# nrf51822.net
KiCad netlist of a schematic drawn in EAGLE
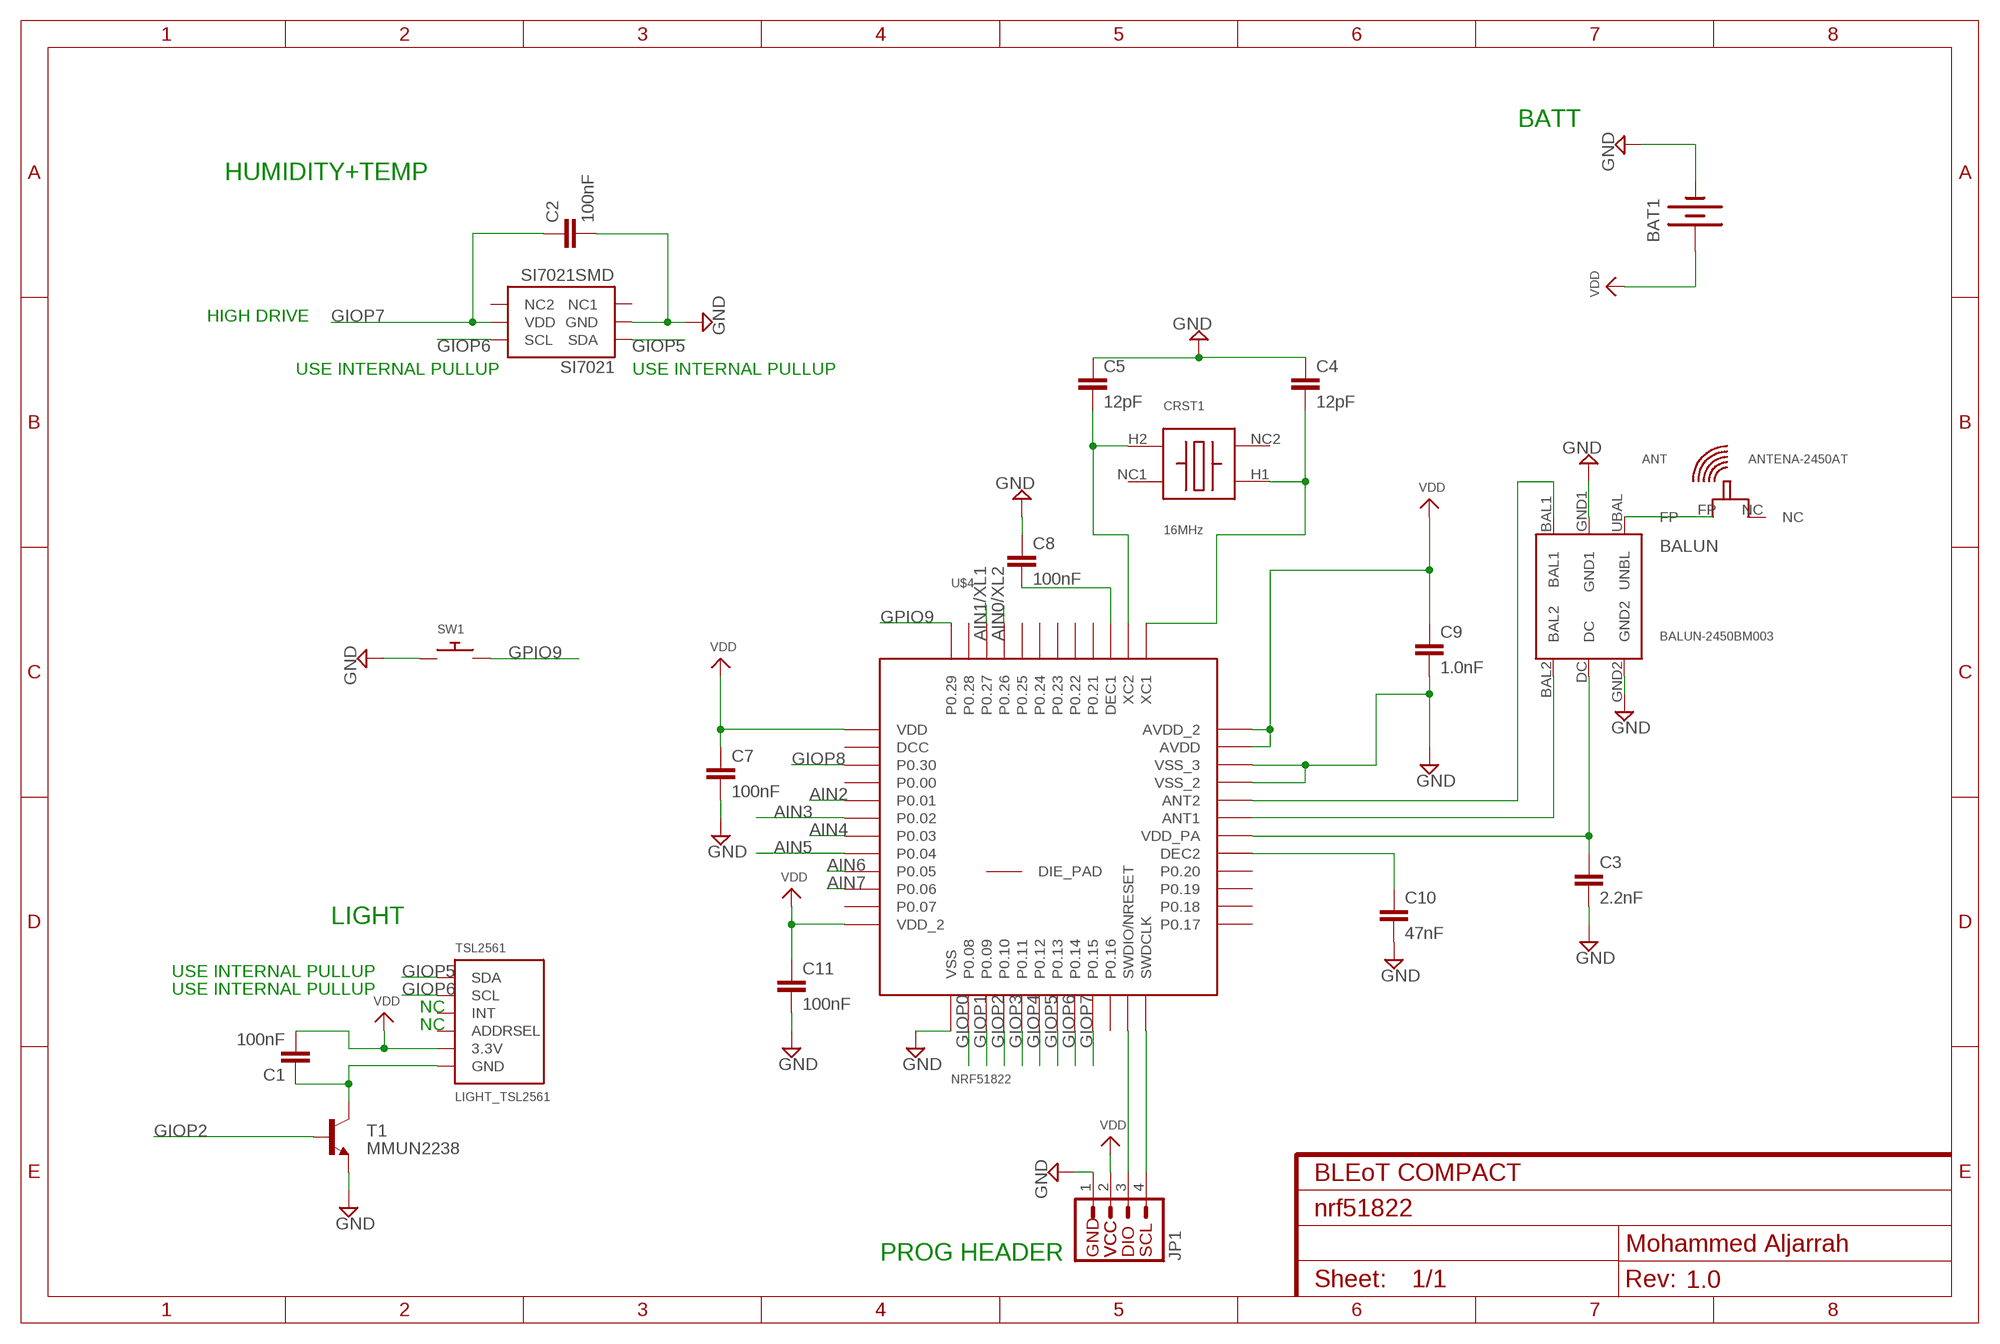
[diagram p0: schematic, sheet 1]

(export (version "E")
  (design (tool "Eeschema 10.0.6"))
  (components
    (comp (ref "ANT")
      (value "ANTENA-2450AT")
      (footprint "eagle-import:2450AT18B100")
      (libsource (lib "eagle-import") (part "ANTENA-2450AT"))
    )
    (comp (ref "BALUN")
      (value "BALUN-2450BM003")
      (footprint "eagle-import:2450BM14E0003")
      (libsource (lib "eagle-import") (part "BALUN-2450BM003"))
    )
    (comp (ref "BAT1")
      (value "BATTERY245PTH")
      (footprint "eagle-import:BATTCON_245MM_PTH")
      (libsource (lib "eagle-import") (part "BATTERY245PTH"))
    )
    (comp (ref "C1")
      (value "100nF")
      (footprint "eagle-import:C0805")
      (libsource (lib "eagle-import") (part "C-EUC0805"))
    )
    (comp (ref "C2")
      (value "100nF")
      (footprint "eagle-import:C0805")
      (libsource (lib "eagle-import") (part "C-EUC0805"))
    )
    (comp (ref "C3")
      (value "2.2nF")
      (footprint "eagle-import:C0805")
      (libsource (lib "eagle-import") (part "C-EUC0805"))
    )
    (comp (ref "C4")
      (value "12pF")
      (footprint "eagle-import:C0805")
      (libsource (lib "eagle-import") (part "C-EUC0805"))
    )
    (comp (ref "C5")
      (value "12pF")
      (footprint "eagle-import:C0805")
      (libsource (lib "eagle-import") (part "C-EUC0805"))
    )
    (comp (ref "C7")
      (value "100nF")
      (footprint "eagle-import:C0805")
      (libsource (lib "eagle-import") (part "C-EUC0805"))
    )
    (comp (ref "C8")
      (value "100nF")
      (footprint "eagle-import:C0805")
      (libsource (lib "eagle-import") (part "C-EUC0805"))
    )
    (comp (ref "C9")
      (value "1.0nF")
      (footprint "eagle-import:C0805")
      (libsource (lib "eagle-import") (part "C-EUC0805"))
    )
    (comp (ref "C10")
      (value "47nF")
      (footprint "eagle-import:C0805")
      (libsource (lib "eagle-import") (part "C-EUC0805"))
    )
    (comp (ref "C11")
      (value "100nF")
      (footprint "eagle-import:C0805")
      (libsource (lib "eagle-import") (part "C-EUC0805"))
    )
    (comp (ref "CRST1")
      (value "16MHz")
      (footprint "eagle-import:CRYSTAL16MHZ")
      (libsource (lib "eagle-import") (part "CX3225GB"))
    )
    (comp (ref "JP1")
      (value "PROG_HEADER")
      (footprint "eagle-import:1X04")
      (libsource (lib "eagle-import") (part "PROG_HEADER"))
    )
    (comp (ref "SI7021")
      (value "SI7021SMD")
      (footprint "eagle-import:SI7021")
      (libsource (lib "eagle-import") (part "SI7021SMD"))
    )
    (comp (ref "SW1")
      (value "SWITCH_PUSHBUTTONSOFTTOUCHSMD_SJ")
      (footprint "eagle-import:PUSHBUTTON_SMD_SJ")
      (libsource (lib "eagle-import") (part "SWITCH_PUSHBUTTONSOFTTOUCHSMD_SJ"))
    )
    (comp (ref "T1")
      (value "MMUN2238")
      (footprint "eagle-import:SOT23-3")
      (libsource (lib "eagle-import") (part "TRANSISTOR_NPNMMBT2222A"))
    )
    (comp (ref "TSL2561")
      (value "LIGHT_TSL2561")
      (footprint "eagle-import:TSL2561_FN")
      (libsource (lib "eagle-import") (part "LIGHT_TSL2561"))
    )
    (comp (ref "U$4")
      (value "NRF51822")
      (footprint "eagle-import:QFN48")
      (libsource (lib "eagle-import") (part "NRF51822"))
    )
  )
  (nets
    (net (code "1") (name "/AIN0{slash}XL2") (class "Default")
      (node (ref "U$4") (pin "45") (pinfunction "P0.26_45") (pintype "bidirectional"))
    )
    (net (code "2") (name "/AIN1{slash}XL1") (class "Default")
      (node (ref "U$4") (pin "46") (pinfunction "P0.27_46") (pintype "bidirectional"))
    )
    (net (code "3") (name "/AIN2") (class "Default")
      (node (ref "U$4") (pin "5") (pinfunction "P0.01_5") (pintype "bidirectional"))
    )
    (net (code "4") (name "/AIN3") (class "Default")
      (node (ref "U$4") (pin "6") (pinfunction "P0.02_6") (pintype "bidirectional"))
    )
    (net (code "5") (name "/AIN4") (class "Default")
      (node (ref "U$4") (pin "7") (pinfunction "P0.03_7") (pintype "bidirectional"))
    )
    (net (code "6") (name "/AIN5") (class "Default")
      (node (ref "U$4") (pin "8") (pinfunction "P0.04_8") (pintype "bidirectional"))
    )
    (net (code "7") (name "/AIN6") (class "Default")
      (node (ref "U$4") (pin "9") (pinfunction "P0.05_9") (pintype "bidirectional"))
    )
    (net (code "8") (name "/AIN7") (class "Default")
      (node (ref "U$4") (pin "10") (pinfunction "P0.06_10") (pintype "bidirectional"))
    )
    (net (code "9") (name "/GIOP0") (class "Default")
      (node (ref "U$4") (pin "14") (pinfunction "P0.08_14") (pintype "bidirectional"))
    )
    (net (code "10") (name "/GIOP1") (class "Default")
      (node (ref "U$4") (pin "15") (pinfunction "P0.09_15") (pintype "bidirectional"))
    )
    (net (code "11") (name "/GIOP2") (class "Default")
      (node (ref "T1") (pin "1") (pinfunction "B_1") (pintype "passive"))
      (node (ref "U$4") (pin "16") (pinfunction "P0.10_16") (pintype "bidirectional"))
    )
    (net (code "12") (name "/GIOP3") (class "Default")
      (node (ref "U$4") (pin "17") (pinfunction "P0.11_17") (pintype "bidirectional"))
    )
    (net (code "13") (name "/GIOP4") (class "Default")
      (node (ref "U$4") (pin "18") (pinfunction "P0.12_18") (pintype "bidirectional"))
    )
    (net (code "14") (name "/GIOP5") (class "Default")
      (node (ref "SI7021") (pin "1") (pinfunction "SDA_1") (pintype "bidirectional"))
      (node (ref "TSL2561") (pin "DATA") (pinfunction "SDA_DATA") (pintype "bidirectional"))
      (node (ref "U$4") (pin "19") (pinfunction "P0.13_19") (pintype "bidirectional"))
    )
    (net (code "15") (name "/GIOP6") (class "Default")
      (node (ref "SI7021") (pin "6") (pinfunction "SCL_6") (pintype "bidirectional"))
      (node (ref "TSL2561") (pin "CLK") (pinfunction "SCL_CLK") (pintype "bidirectional"))
      (node (ref "U$4") (pin "20") (pinfunction "P0.14_20") (pintype "bidirectional"))
    )
    (net (code "16") (name "/GIOP7") (class "Default")
      (node (ref "C2") (pin "1") (pinfunction "1_1") (pintype "passive"))
      (node (ref "SI7021") (pin "5") (pinfunction "VDD_5") (pintype "power_in"))
      (node (ref "U$4") (pin "21") (pinfunction "P0.15_21") (pintype "bidirectional"))
    )
    (net (code "17") (name "/GIOP8") (class "Default")
      (node (ref "U$4") (pin "3") (pinfunction "P0.30_3") (pintype "bidirectional"))
    )
    (net (code "18") (name "/GPIO9") (class "Default")
      (node (ref "SW1") (pin "P$2") (pinfunction "P$2_P$2") (pintype "passive"))
      (node (ref "U$4") (pin "48") (pinfunction "P0.29_48") (pintype "bidirectional"))
    )
    (net (code "19") (name "GND") (class "Default")
      (node (ref "BALUN") (pin "GND1") (pinfunction "GND1_GND1") (pintype "power_in"))
      (node (ref "BALUN") (pin "GND2") (pinfunction "GND2_GND2") (pintype "power_in"))
      (node (ref "BAT1") (pin "2") (pinfunction "-_2") (pintype "power_in"))
      (node (ref "C10") (pin "2") (pinfunction "2_2") (pintype "passive"))
      (node (ref "C11") (pin "2") (pinfunction "2_2") (pintype "passive"))
      (node (ref "C2") (pin "2") (pinfunction "2_2") (pintype "passive"))
      (node (ref "C3") (pin "2") (pinfunction "2_2") (pintype "passive"))
      (node (ref "C4") (pin "1") (pinfunction "1_1") (pintype "passive"))
      (node (ref "C5") (pin "1") (pinfunction "1_1") (pintype "passive"))
      (node (ref "C7") (pin "2") (pinfunction "2_2") (pintype "passive"))
      (node (ref "C8") (pin "1") (pinfunction "1_1") (pintype "passive"))
      (node (ref "C9") (pin "2") (pinfunction "2_2") (pintype "passive"))
      (node (ref "JP1") (pin "1") (pinfunction "1_1") (pintype "passive"))
      (node (ref "SI7021") (pin "2") (pinfunction "GND_2") (pintype "power_in"))
      (node (ref "SW1") (pin "P$1") (pinfunction "P$1_P$1") (pintype "passive"))
      (node (ref "T1") (pin "2") (pinfunction "E_2") (pintype "passive"))
      (node (ref "U$4") (pin "13") (pinfunction "VSS_13") (pintype "power_in"))
      (node (ref "U$4") (pin "33") (pinfunction "VSS_2_33") (pintype "power_in"))
      (node (ref "U$4") (pin "34") (pinfunction "VSS_3_34") (pintype "power_in"))
    )
    (net (code "20") (name "Net-(BALUN-UNBL)") (class "Default")
      (node (ref "ANT") (pin "FP") (pinfunction "FP_FP") (pintype "input"))
      (node (ref "BALUN") (pin "UBAL") (pinfunction "UNBL_UBAL") (pintype "output"))
    )
    (net (code "21") (name "Net-(T1-C)") (class "Default")
      (node (ref "C1") (pin "1") (pinfunction "1_1") (pintype "passive"))
      (node (ref "T1") (pin "3") (pinfunction "C_3") (pintype "passive"))
      (node (ref "TSL2561") (pin "VSS") (pinfunction "GND_VSS") (pintype "bidirectional"))
    )
    (net (code "22") (name "Net-(U$4-ANT1)") (class "Default")
      (node (ref "BALUN") (pin "BAL2") (pinfunction "BAL2_BAL2") (pintype "input"))
      (node (ref "U$4") (pin "31") (pinfunction "ANT1_31") (pintype "bidirectional"))
    )
    (net (code "23") (name "Net-(U$4-ANT2)") (class "Default")
      (node (ref "BALUN") (pin "BAL1") (pinfunction "BAL1_BAL1") (pintype "input"))
      (node (ref "U$4") (pin "32") (pinfunction "ANT2_32") (pintype "bidirectional"))
    )
    (net (code "24") (name "Net-(U$4-DEC1)") (class "Default")
      (node (ref "C8") (pin "2") (pinfunction "2_2") (pintype "passive"))
      (node (ref "U$4") (pin "39") (pinfunction "DEC1_39") (pintype "bidirectional"))
    )
    (net (code "25") (name "Net-(U$4-DEC2)") (class "Default")
      (node (ref "C10") (pin "1") (pinfunction "1_1") (pintype "passive"))
      (node (ref "U$4") (pin "29") (pinfunction "DEC2_29") (pintype "bidirectional"))
    )
    (net (code "26") (name "Net-(U$4-SWDCLK)") (class "Default")
      (node (ref "JP1") (pin "4") (pinfunction "4_4") (pintype "passive"))
      (node (ref "U$4") (pin "24") (pinfunction "SWDCLK_24") (pintype "bidirectional"))
    )
    (net (code "27") (name "Net-(U$4-SWDIO{slash}NRESET)") (class "Default")
      (node (ref "JP1") (pin "3") (pinfunction "3_3") (pintype "passive"))
      (node (ref "U$4") (pin "23") (pinfunction "SWDIO/NRESET_23") (pintype "bidirectional"))
    )
    (net (code "28") (name "Net-(U$4-VDD_PA)") (class "Default")
      (node (ref "BALUN") (pin "DC") (pinfunction "DC_DC") (pintype "power_in"))
      (node (ref "C3") (pin "1") (pinfunction "1_1") (pintype "passive"))
      (node (ref "U$4") (pin "30") (pinfunction "VDD_PA_30") (pintype "bidirectional"))
    )
    (net (code "29") (name "Net-(U$4-XC1)") (class "Default")
      (node (ref "C4") (pin "2") (pinfunction "2_2") (pintype "passive"))
      (node (ref "CRST1") (pin "H1") (pinfunction "H1_H1") (pintype "input"))
      (node (ref "U$4") (pin "37") (pinfunction "XC1_37") (pintype "bidirectional"))
    )
    (net (code "30") (name "Net-(U$4-XC2)") (class "Default")
      (node (ref "C5") (pin "2") (pinfunction "2_2") (pintype "passive"))
      (node (ref "CRST1") (pin "H2") (pinfunction "H2_H2") (pintype "input"))
      (node (ref "U$4") (pin "38") (pinfunction "XC2_38") (pintype "bidirectional"))
    )
    (net (code "31") (name "VDD") (class "Default")
      (node (ref "BAT1") (pin "1") (pinfunction "+_1") (pintype "power_in"))
      (node (ref "BAT1") (pin "3") (pinfunction "+_3") (pintype "power_in"))
      (node (ref "C1") (pin "2") (pinfunction "2_2") (pintype "passive"))
      (node (ref "C11") (pin "1") (pinfunction "1_1") (pintype "passive"))
      (node (ref "C7") (pin "1") (pinfunction "1_1") (pintype "passive"))
      (node (ref "C9") (pin "1") (pinfunction "1_1") (pintype "passive"))
      (node (ref "JP1") (pin "2") (pinfunction "2_2") (pintype "passive"))
      (node (ref "TSL2561") (pin "VDD") (pinfunction "3.3V_VDD") (pintype "bidirectional"))
      (node (ref "U$4") (pin "1") (pinfunction "VDD_1") (pintype "power_in"))
      (node (ref "U$4") (pin "12") (pinfunction "VDD_2_12") (pintype "power_in"))
      (node (ref "U$4") (pin "35") (pinfunction "AVDD_35") (pintype "power_in"))
      (node (ref "U$4") (pin "36") (pinfunction "AVDD_2_36") (pintype "power_in"))
    )
    (net (code "32") (name "unconnected-(ANT-PadNC)") (class "Default")
      (node (ref "ANT") (pin "NC") (pinfunction "NC_NC") (pintype "no_connect"))
    )
    (net (code "33") (name "unconnected-(CRST1-PadNC1)") (class "Default")
      (node (ref "CRST1") (pin "NC1") (pinfunction "NC1_NC1") (pintype "no_connect"))
    )
    (net (code "34") (name "unconnected-(CRST1-PadNC2)") (class "Default")
      (node (ref "CRST1") (pin "NC2") (pinfunction "NC2_NC2") (pintype "no_connect"))
    )
    (net (code "35") (name "unconnected-(SI7021-NC1-Pad3)") (class "Default")
      (node (ref "SI7021") (pin "3") (pinfunction "NC1_3") (pintype "no_connect"))
    )
    (net (code "36") (name "unconnected-(SI7021-NC2-Pad4)") (class "Default")
      (node (ref "SI7021") (pin "4") (pinfunction "NC2_4") (pintype "no_connect"))
    )
    (net (code "37") (name "unconnected-(TSL2561-ADDRSEL-PadADR)") (class "Default")
      (node (ref "TSL2561") (pin "ADR") (pinfunction "ADDRSEL_ADR") (pintype "bidirectional"))
    )
    (net (code "38") (name "unconnected-(TSL2561-PadINT)") (class "Default")
      (node (ref "TSL2561") (pin "INT") (pinfunction "INT_INT") (pintype "bidirectional"))
    )
    (net (code "39") (name "unconnected-(U$4-DCC-Pad2)") (class "Default")
      (node (ref "U$4") (pin "2") (pinfunction "DCC_2") (pintype "no_connect"))
    )
    (net (code "40") (name "unconnected-(U$4-DIE_PAD-PadGND)") (class "Default")
      (node (ref "U$4") (pin "GND") (pinfunction "DIE_PAD_GND") (pintype "bidirectional"))
    )
    (net (code "41") (name "unconnected-(U$4-P0.00-Pad4)") (class "Default")
      (node (ref "U$4") (pin "4") (pinfunction "P0.00_4") (pintype "bidirectional"))
    )
    (net (code "42") (name "unconnected-(U$4-P0.07-Pad11)") (class "Default")
      (node (ref "U$4") (pin "11") (pinfunction "P0.07_11") (pintype "bidirectional"))
    )
    (net (code "43") (name "unconnected-(U$4-P0.16-Pad22)") (class "Default")
      (node (ref "U$4") (pin "22") (pinfunction "P0.16_22") (pintype "bidirectional"))
    )
    (net (code "44") (name "unconnected-(U$4-P0.17-Pad25)") (class "Default")
      (node (ref "U$4") (pin "25") (pinfunction "P0.17_25") (pintype "bidirectional"))
    )
    (net (code "45") (name "unconnected-(U$4-P0.18-Pad26)") (class "Default")
      (node (ref "U$4") (pin "26") (pinfunction "P0.18_26") (pintype "bidirectional"))
    )
    (net (code "46") (name "unconnected-(U$4-P0.19-Pad27)") (class "Default")
      (node (ref "U$4") (pin "27") (pinfunction "P0.19_27") (pintype "bidirectional"))
    )
    (net (code "47") (name "unconnected-(U$4-P0.20-Pad28)") (class "Default")
      (node (ref "U$4") (pin "28") (pinfunction "P0.20_28") (pintype "bidirectional"))
    )
    (net (code "48") (name "unconnected-(U$4-P0.21-Pad40)") (class "Default")
      (node (ref "U$4") (pin "40") (pinfunction "P0.21_40") (pintype "bidirectional"))
    )
    (net (code "49") (name "unconnected-(U$4-P0.22-Pad41)") (class "Default")
      (node (ref "U$4") (pin "41") (pinfunction "P0.22_41") (pintype "bidirectional"))
    )
    (net (code "50") (name "unconnected-(U$4-P0.23-Pad42)") (class "Default")
      (node (ref "U$4") (pin "42") (pinfunction "P0.23_42") (pintype "bidirectional"))
    )
    (net (code "51") (name "unconnected-(U$4-P0.24-Pad43)") (class "Default")
      (node (ref "U$4") (pin "43") (pinfunction "P0.24_43") (pintype "bidirectional"))
    )
    (net (code "52") (name "unconnected-(U$4-P0.25-Pad44)") (class "Default")
      (node (ref "U$4") (pin "44") (pinfunction "P0.25_44") (pintype "bidirectional"))
    )
    (net (code "53") (name "unconnected-(U$4-P0.28-Pad47)") (class "Default")
      (node (ref "U$4") (pin "47") (pinfunction "P0.28_47") (pintype "bidirectional"))
    )
  )
)
